# GD_Tcontroller_Power.net
KiCad netlist of a schematic drawn in Altium Designer
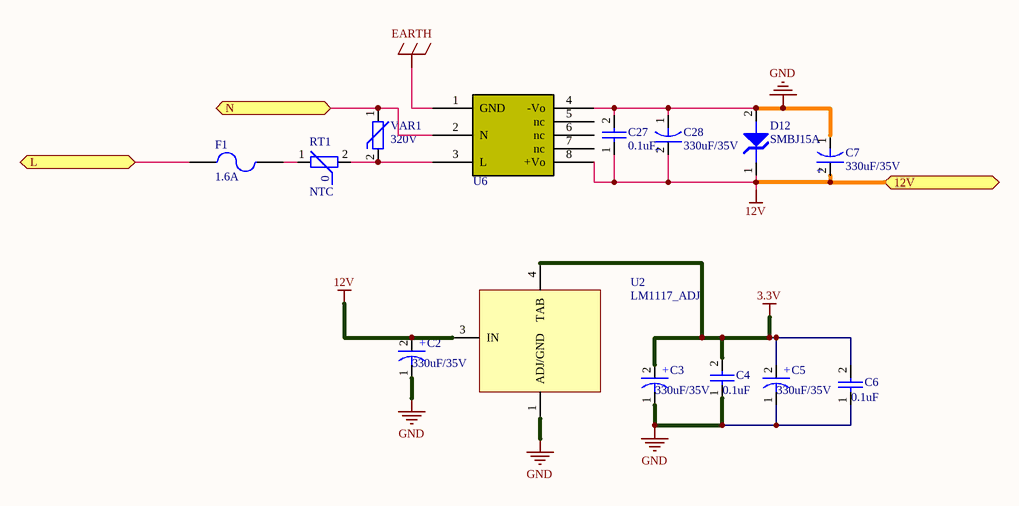
[diagram p0: GD_Tcontroller_Power.SchDoc]

(export (version "E")
  (design (tool "Eeschema 10.0.6"))
  (components
    (comp (ref "C2")
      (value "330uF/35V")
      (footprint "CA10X16P5")
      (description "CAP 35V 20% 330uF 10X16X0.6MM ROHS，7000hours")
      (fields (field (name "MANUFACTURER") "NIPPON CHEMI-CON") (field (name "Comment") "CAPACITOR"))
      (libsource (lib "Enlogic") (part "CAPACITOR"))
    )
    (comp (ref "C3")
      (value "330uF/35V")
      (footprint "CA10X16P5")
      (description "CAP 35V 20% 330uF 10X16X0.6MM ROHS，7000hours")
      (fields (field (name "MANUFACTURER") "NIPPON CHEMI-CON") (field (name "Comment") "CAPACITOR"))
      (libsource (lib "Enlogic") (part "CAPACITOR"))
    )
    (comp (ref "C4")
      (value "0.1uF")
      (footprint "C0805")
      (description "CAP SMD CR X7R 50V 10% 0.1uF 0805 ROHS")
      (fields (field (name "MANUFACTURER") "YAGEO") (field (name "Comment") "CAP"))
      (libsource (lib "enlogic") (part "CAP"))
    )
    (comp (ref "C5")
      (value "330uF/35V")
      (footprint "CA10X16P5")
      (description "CAP 35V 20% 330uF 10X16X0.6MM ROHS，7000hours")
      (fields (field (name "MANUFACTURER") "NIPPON CHEMI-CON") (field (name "Comment") "CAPACITOR"))
      (libsource (lib "Enlogic") (part "CAPACITOR"))
    )
    (comp (ref "C6")
      (value "0.1uF")
      (footprint "C0805")
      (description "CAP SMD CR X7R 50V 10% 0.1uF 0805 ROHS")
      (fields (field (name "MANUFACTURER") "YAGEO") (field (name "Comment") "CAP"))
      (libsource (lib "enlogic") (part "CAP"))
    )
    (comp (ref "C7")
      (value "330uF/35V")
      (footprint "CA10X16P5")
      (description "CAP 35V 20% 330uF 10X16X0.6MM ROHS，7000hours")
      (fields (field (name "MANUFACTURER") "NIPPON CHEMI-CON") (field (name "Comment") "CAPACITOR"))
      (libsource (lib "Enlogic") (part "CAPACITOR"))
    )
    (comp (ref "C27")
      (value "0.1uF")
      (footprint "C0805")
      (description "CAP SMD CR X7R 50V 10% 0.1uF 0805 ROHS")
      (fields (field (name "MANUFACTURER") "YAGEO") (field (name "Comment") "CAP"))
      (libsource (lib "enlogic") (part "CAP"))
    )
    (comp (ref "C28")
      (value "330uF/35V")
      (footprint "CA10X16P5")
      (description "CAP 35V 20% 330uF 10X16X0.6MM ROHS，7000hours")
      (fields (field (name "MANUFACTURER") "NIPPON CHEMI-CON") (field (name "Comment") "CAPACITOR"))
      (libsource (lib "Enlogic") (part "CAPACITOR"))
    )
    (comp (ref "D12")
      (value "SMBJ15A")
      (footprint "SMB")
      (fields (field (name "MANUFACTURER") "Bourns"))
      (libsource (lib "Enlogic") (part "ZENER"))
    )
    (comp (ref "F1")
      (value "1.6A")
      (footprint "392XXXX000")
      (description "FUSE,Ceramic,1.6A,25A@250VAC,8.5x8mm,ROHS")
      (fields (field (name "MANUFACTURER") "LITTELFUSE") (field (name "Comment") "Fuse"))
      (libsource (lib "Enlogic") (part "Fuse"))
    )
    (comp (ref "RT1")
      (value "NTC")
      (footprint "NTC8_5x6P5")
      (fields (field (name "MANUFACTURER") "SEMITEC"))
      (libsource (lib "Enlogic") (part "NTC"))
    )
    (comp (ref "U2")
      (value "LM1117_ADJ")
      (footprint "DPAK-134")
      (description "IC REG VOLT +3.3V LDO 800MA DPAK ROHS")
      (fields (field (name "MANUFACTURER") "ST"))
      (libsource (lib "Enlogic") (part "LM1117_ADJ"))
    )
    (comp (ref "U6")
      (value "LH05-10B12")
      (footprint "LH05X")
      (fields (field (name "MANUFACTURER") "Mornsun"))
      (libsource (lib "Schlib1") (part "LH05-10B05"))
    )
    (comp (ref "VAR1")
      (value "320V")
      (footprint "VAR16_7X6_6P7_5")
      (description "MOV 320V 14MM 80J LDFR ROHS")
      (fields (field (name "MANUFACTURER") "LITTELFUSE") (field (name "Comment") "VARISTOR"))
      (libsource (lib "Enlogic") (part "VARISTOR"))
    )
  )
  (nets
    (net (code "1") (name "/L") (class "Default")
      (node (ref "F1") (pin "1") (pinfunction "1_1") (pintype "passive"))
    )
    (net (code "2") (name "/N") (class "Default")
      (node (ref "U6") (pin "2") (pinfunction "N_2") (pintype "passive"))
      (node (ref "VAR1") (pin "1") (pinfunction "1_1") (pintype "passive"))
    )
    (net (code "3") (name "3.3V") (class "Default")
      (node (ref "C3") (pin "2") (pinfunction "2_2") (pintype "passive"))
      (node (ref "C4") (pin "2") (pinfunction "2_2") (pintype "passive"))
      (node (ref "C5") (pin "2") (pinfunction "2_2") (pintype "passive"))
      (node (ref "C6") (pin "2") (pinfunction "2_2") (pintype "passive"))
      (node (ref "U2") (pin "4") (pinfunction "TAB_4") (pintype "passive"))
    )
    (net (code "4") (name "12V") (class "Default")
      (node (ref "C2") (pin "2") (pinfunction "2_2") (pintype "passive"))
      (node (ref "C27") (pin "1") (pinfunction "1_1") (pintype "passive"))
      (node (ref "C28") (pin "2") (pinfunction "2_2") (pintype "passive"))
      (node (ref "C7") (pin "2") (pinfunction "2_2") (pintype "passive"))
      (node (ref "D12") (pin "1") (pintype "passive"))
      (node (ref "U2") (pin "3") (pinfunction "IN_3") (pintype "passive"))
      (node (ref "U6") (pin "8") (pinfunction "+Vo_8") (pintype "passive"))
    )
    (net (code "5") (name "EARTH") (class "Default")
      (node (ref "U6") (pin "1") (pinfunction "GND_1") (pintype "passive"))
    )
    (net (code "6") (name "GND") (class "Default")
      (node (ref "C2") (pin "1") (pinfunction "1_1") (pintype "passive"))
      (node (ref "C27") (pin "2") (pinfunction "2_2") (pintype "passive"))
      (node (ref "C28") (pin "1") (pinfunction "1_1") (pintype "passive"))
      (node (ref "C3") (pin "1") (pinfunction "1_1") (pintype "passive"))
      (node (ref "C4") (pin "1") (pinfunction "1_1") (pintype "passive"))
      (node (ref "C5") (pin "1") (pinfunction "1_1") (pintype "passive"))
      (node (ref "C6") (pin "1") (pinfunction "1_1") (pintype "passive"))
      (node (ref "C7") (pin "1") (pinfunction "1_1") (pintype "passive"))
      (node (ref "D12") (pin "2") (pintype "passive"))
      (node (ref "U2") (pin "1") (pinfunction "ADJ/GND_1") (pintype "passive"))
      (node (ref "U6") (pin "4") (pinfunction "-Vo_4") (pintype "passive"))
    )
    (net (code "7") (name "Net-(F1-Pad2)") (class "Default")
      (node (ref "F1") (pin "2") (pinfunction "2_2") (pintype "passive"))
      (node (ref "RT1") (pin "1") (pinfunction "1_1") (pintype "passive"))
    )
    (net (code "8") (name "Net-(U6-L)") (class "Default")
      (node (ref "RT1") (pin "2") (pinfunction "2_2") (pintype "passive"))
      (node (ref "U6") (pin "3") (pinfunction "L_3") (pintype "passive"))
      (node (ref "VAR1") (pin "2") (pinfunction "2_2") (pintype "passive"))
    )
    (net (code "9") (name "unconnected-(U6-nc-Pad5)") (class "Default")
      (node (ref "U6") (pin "5") (pinfunction "nc_5") (pintype "passive"))
    )
    (net (code "10") (name "unconnected-(U6-nc-Pad6)") (class "Default")
      (node (ref "U6") (pin "6") (pinfunction "nc_6") (pintype "passive"))
    )
    (net (code "11") (name "unconnected-(U6-nc-Pad7)") (class "Default")
      (node (ref "U6") (pin "7") (pinfunction "nc_7") (pintype "passive"))
    )
  )
)
